# IO_PWR_FMU_REV_1B.net
KiCad netlist of a schematic drawn in Altium Designer
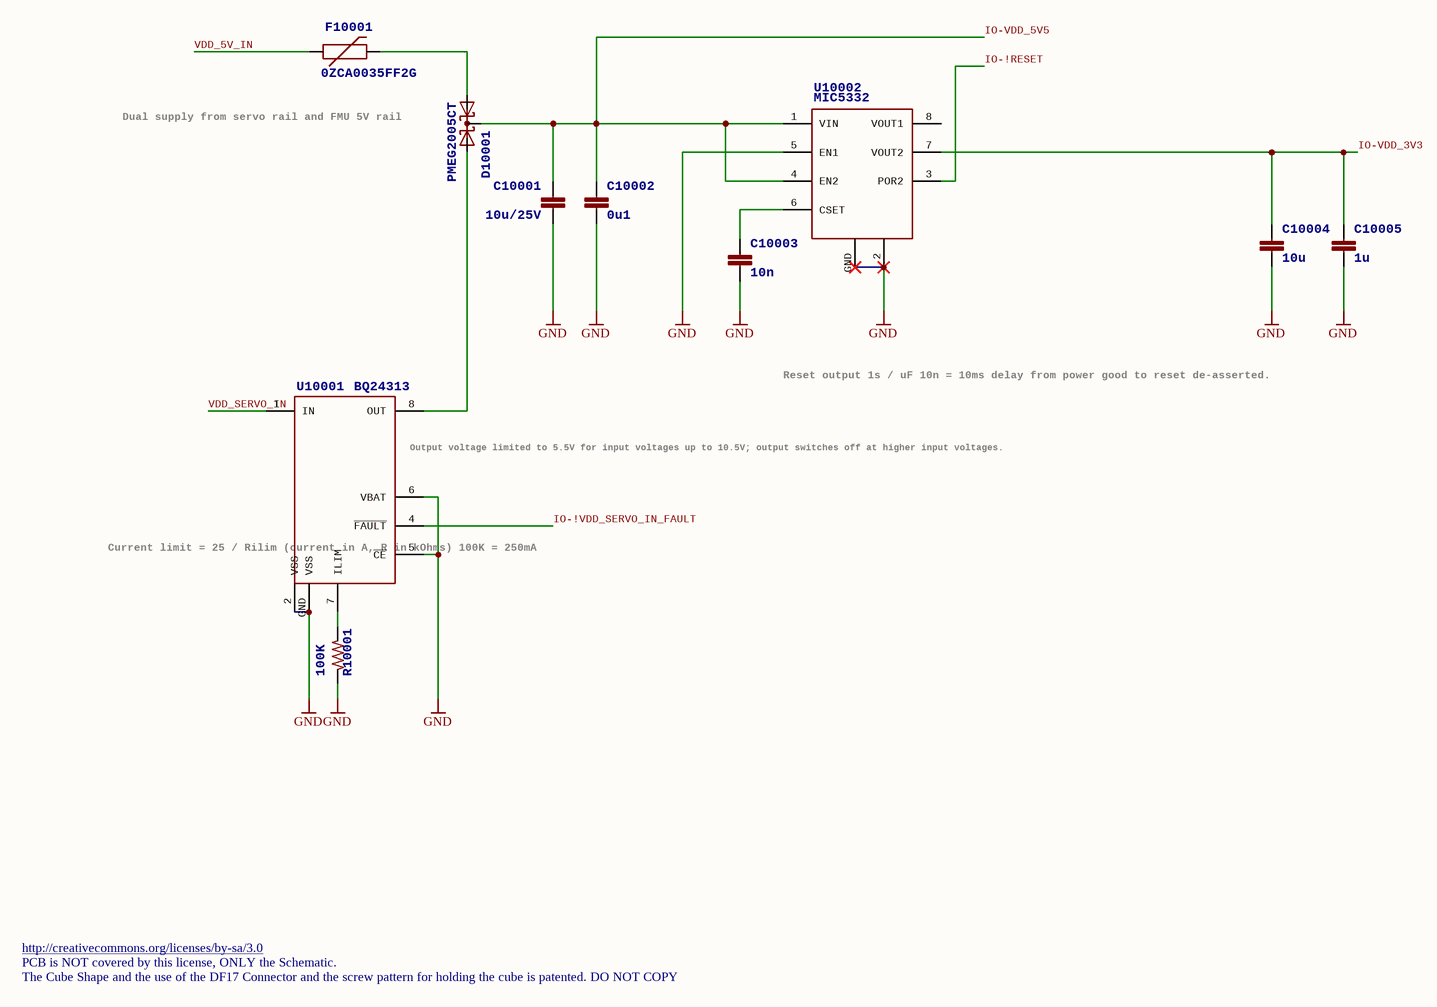
[diagram p0: IO_PWR_FMU_REV_1B.SchDoc]

(export (version "E")
  (design (tool "Eeschema 10.0.6"))
  (components
    (comp (ref "C10001")
      (value "10u/25V")
      (footprint "0805-CAP")
      (description "CAP CER 10UF 25V 10% X5R 0805")
      (libsource (lib "pixhawk2") (part "CAP0805"))
    )
    (comp (ref "C10002")
      (value "0u1")
      (footprint "0402-CAP")
      (description "CAP CER 0.1UF 16V Y5V 0402")
      (libsource (lib "pixhawk2") (part "CAP0402"))
    )
    (comp (ref "C10003")
      (value "10n")
      (footprint "0402-CAP")
      (description "CAP CER 10000PF 16V 10% X7R 0402")
      (libsource (lib "pixhawk2") (part "CAP0402"))
    )
    (comp (ref "C10004")
      (value "10u")
      (footprint "0603-CAP")
      (description "CAP CER 10UF 10V 10% X5R 0603")
      (libsource (lib "pixhawk2") (part "CAP0603"))
    )
    (comp (ref "C10005")
      (value "1u")
      (footprint "0603-CAP")
      (description "CAP CER 1UF 16V Y5V 0603")
      (libsource (lib "pixhawk2") (part "CAP0603"))
    )
    (comp (ref "D10001")
      (value "PMEG2005CT")
      (footprint "SOT23-3")
      (description "DIODE SCHOTTKY 20V 500MA TO236AB")
      (libsource (lib "pixhawk2") (part "PMEG2005CT"))
    )
    (comp (ref "F10001")
      (value "0ZCA0035FF2G")
      (footprint "PTC-1206")
      (description "PTC RESTTBLE 0.35A 16V CHIP 1206")
      (libsource (lib "pixhawk2") (part "PTCSMD"))
    )
    (comp (ref "R10001")
      (value "100K")
      (footprint "0402-RES")
      (description "RES 100K OHM 1/16W 1% 0402 SMD")
      (libsource (lib "pixhawk2") (part "RESISTOR0402-RES"))
    )
    (comp (ref "U10001")
      (value "BQ24313")
      (footprint "QFN8-DSG")
      (description "IC LI+ CHARGER FRONT END 8-SON")
      (libsource (lib "pixhawk2") (part "BQ24313"))
    )
    (comp (ref "U10002")
      (value "MIC5332")
      (footprint "MLF-8-EPAD")
      (description "IC REG LDO 3.3V 0.3A 8TMLF")
      (libsource (lib "pixhawk2") (part "MIC5332"))
    )
  )
  (nets
    (net (code "1") (name "/IO-!RESET") (class "Default")
      (node (ref "U10002") (pin "3") (pinfunction "POR2_3") (pintype "passive"))
    )
    (net (code "2") (name "/IO-!VDD_SERVO_IN_FAULT") (class "Default")
      (node (ref "U10001") (pin "4") (pinfunction "~{FAULT}_4") (pintype "passive"))
    )
    (net (code "3") (name "/IO-VDD_3V3") (class "Default")
      (node (ref "C10004") (pin "P$1") (pinfunction "1_P$1") (pintype "passive"))
      (node (ref "C10005") (pin "P$1") (pinfunction "1_P$1") (pintype "passive"))
      (node (ref "U10002") (pin "7") (pinfunction "VOUT2_7") (pintype "passive"))
    )
    (net (code "4") (name "/IO-VDD_5V5") (class "Default")
      (node (ref "C10001") (pin "P$1") (pinfunction "1_P$1") (pintype "passive"))
      (node (ref "C10002") (pin "P$1") (pinfunction "1_P$1") (pintype "passive"))
      (node (ref "D10001") (pin "3") (pinfunction "CC_3") (pintype "passive"))
      (node (ref "U10002") (pin "1") (pinfunction "VIN_1") (pintype "passive"))
      (node (ref "U10002") (pin "4") (pinfunction "EN2_4") (pintype "passive"))
    )
    (net (code "5") (name "/VDD_5V_IN") (class "Default")
      (node (ref "F10001") (pin "1") (pinfunction "1_1") (pintype "passive"))
    )
    (net (code "6") (name "/VDD_SERVO_IN") (class "Default")
      (node (ref "U10001") (pin "1") (pinfunction "IN_1") (pintype "passive"))
    )
    (net (code "7") (name "GND") (class "Default")
      (node (ref "C10001") (pin "P$2") (pinfunction "2_P$2") (pintype "passive"))
      (node (ref "C10002") (pin "P$2") (pinfunction "2_P$2") (pintype "passive"))
      (node (ref "C10003") (pin "P$2") (pinfunction "2_P$2") (pintype "passive"))
      (node (ref "C10004") (pin "P$2") (pinfunction "2_P$2") (pintype "passive"))
      (node (ref "C10005") (pin "P$2") (pinfunction "2_P$2") (pintype "passive"))
      (node (ref "R10001") (pin "P$1") (pinfunction "1_P$1") (pintype "passive"))
      (node (ref "U10001") (pin "2") (pinfunction "VSS_2") (pintype "passive"))
      (node (ref "U10001") (pin "5") (pinfunction "~{CE}_5") (pintype "passive"))
      (node (ref "U10001") (pin "6") (pinfunction "VBAT_6") (pintype "passive"))
      (node (ref "U10001") (pin "GND") (pinfunction "VSS_GND") (pintype "passive"))
      (node (ref "U10002") (pin "2") (pinfunction "GND_2") (pintype "power_in"))
      (node (ref "U10002") (pin "5") (pinfunction "EN1_5") (pintype "passive"))
      (node (ref "U10002") (pin "GND") (pinfunction "GND_GND") (pintype "power_in"))
    )
    (net (code "8") (name "Net-(C10003-1)") (class "Default")
      (node (ref "C10003") (pin "P$1") (pinfunction "1_P$1") (pintype "passive"))
      (node (ref "U10002") (pin "6") (pinfunction "CSET_6") (pintype "passive"))
    )
    (net (code "9") (name "Net-(D10001-A1)") (class "Default")
      (node (ref "D10001") (pin "1") (pinfunction "A1_1") (pintype "passive"))
      (node (ref "F10001") (pin "2") (pinfunction "2_2") (pintype "passive"))
    )
    (net (code "10") (name "Net-(D10001-A2)") (class "Default")
      (node (ref "D10001") (pin "2") (pinfunction "A2_2") (pintype "passive"))
      (node (ref "U10001") (pin "8") (pinfunction "OUT_8") (pintype "passive"))
    )
    (net (code "11") (name "Net-(R10001-2)") (class "Default")
      (node (ref "R10001") (pin "P$2") (pinfunction "2_P$2") (pintype "passive"))
      (node (ref "U10001") (pin "7") (pinfunction "ILIM_7") (pintype "passive"))
    )
    (net (code "12") (name "unconnected-(U10002-VOUT1-Pad8)") (class "Default")
      (node (ref "U10002") (pin "8") (pinfunction "VOUT1_8") (pintype "passive"))
    )
  )
)
